# Nexys_2_Port_Expansion_Pack.net
KiCad netlist of a schematic drawn in EAGLE
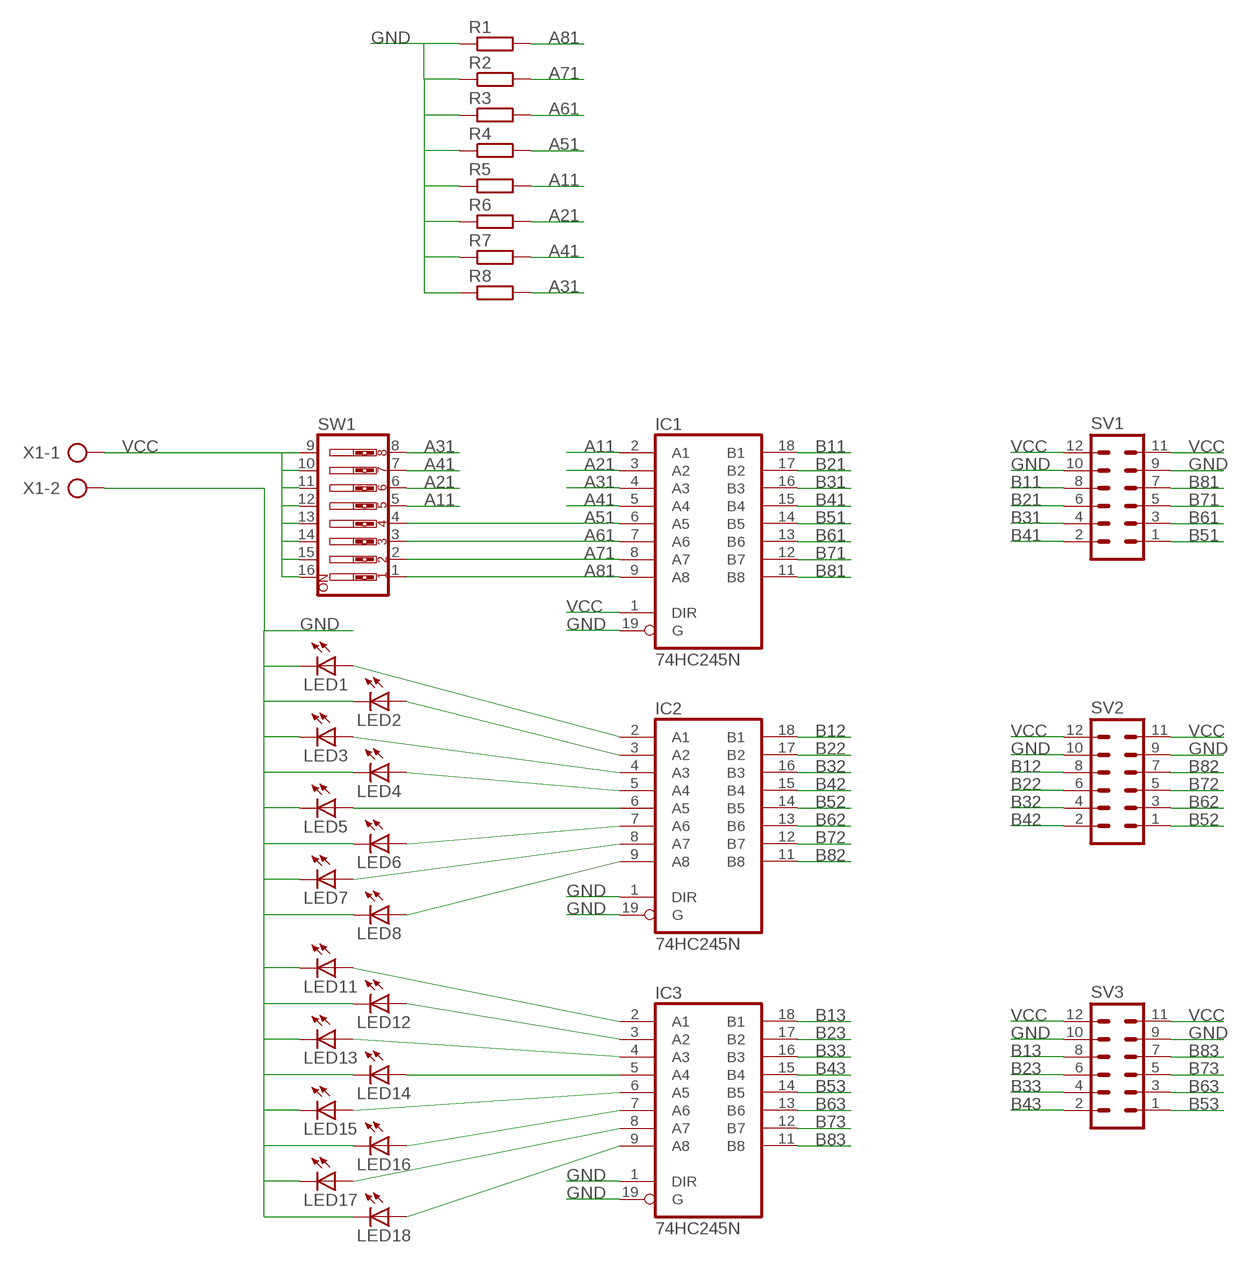
[diagram p0: schematic, sheet 1]

(export (version "E")
  (design (tool "Eeschema 10.0.6"))
  (components
    (comp (ref "IC1")
      (value "74HC245N")
      (footprint "eagle-import:DIL20")
      (libsource (lib "eagle-import") (part "74245NHC"))
    )
    (comp (ref "IC2")
      (value "74HC245N")
      (footprint "eagle-import:DIL20")
      (libsource (lib "eagle-import") (part "74245NHC"))
    )
    (comp (ref "IC3")
      (value "74HC245N")
      (footprint "eagle-import:DIL20")
      (libsource (lib "eagle-import") (part "74245NHC"))
    )
    (comp (ref "LED1")
      (value "LED3MM")
      (footprint "eagle-import:LED3MM")
      (libsource (lib "eagle-import") (part "LED3MM"))
    )
    (comp (ref "LED2")
      (value "LED3MM")
      (footprint "eagle-import:LED3MM")
      (libsource (lib "eagle-import") (part "LED3MM"))
    )
    (comp (ref "LED3")
      (value "LED3MM")
      (footprint "eagle-import:LED3MM")
      (libsource (lib "eagle-import") (part "LED3MM"))
    )
    (comp (ref "LED4")
      (value "LED3MM")
      (footprint "eagle-import:LED3MM")
      (libsource (lib "eagle-import") (part "LED3MM"))
    )
    (comp (ref "LED5")
      (value "LED3MM")
      (footprint "eagle-import:LED3MM")
      (libsource (lib "eagle-import") (part "LED3MM"))
    )
    (comp (ref "LED6")
      (value "LED3MM")
      (footprint "eagle-import:LED3MM")
      (libsource (lib "eagle-import") (part "LED3MM"))
    )
    (comp (ref "LED7")
      (value "LED3MM")
      (footprint "eagle-import:LED3MM")
      (libsource (lib "eagle-import") (part "LED3MM"))
    )
    (comp (ref "LED8")
      (value "LED3MM")
      (footprint "eagle-import:LED3MM")
      (libsource (lib "eagle-import") (part "LED3MM"))
    )
    (comp (ref "LED11")
      (value "LED3MM")
      (footprint "eagle-import:LED3MM")
      (libsource (lib "eagle-import") (part "LED3MM"))
    )
    (comp (ref "LED12")
      (value "LED3MM")
      (footprint "eagle-import:LED3MM")
      (libsource (lib "eagle-import") (part "LED3MM"))
    )
    (comp (ref "LED13")
      (value "LED3MM")
      (footprint "eagle-import:LED3MM")
      (libsource (lib "eagle-import") (part "LED3MM"))
    )
    (comp (ref "LED14")
      (value "LED3MM")
      (footprint "eagle-import:LED3MM")
      (libsource (lib "eagle-import") (part "LED3MM"))
    )
    (comp (ref "LED15")
      (value "LED3MM")
      (footprint "eagle-import:LED3MM")
      (libsource (lib "eagle-import") (part "LED3MM"))
    )
    (comp (ref "LED16")
      (value "LED3MM")
      (footprint "eagle-import:LED3MM")
      (libsource (lib "eagle-import") (part "LED3MM"))
    )
    (comp (ref "LED17")
      (value "LED3MM")
      (footprint "eagle-import:LED3MM")
      (libsource (lib "eagle-import") (part "LED3MM"))
    )
    (comp (ref "LED18")
      (value "LED3MM")
      (footprint "eagle-import:LED3MM")
      (libsource (lib "eagle-import") (part "LED3MM"))
    )
    (comp (ref "R1")
      (value "R-EU_0207/15")
      (footprint "eagle-import:0207_15")
      (libsource (lib "eagle-import") (part "R-EU_0207/15"))
    )
    (comp (ref "R2")
      (value "R-EU_0207/15")
      (footprint "eagle-import:0207_15")
      (libsource (lib "eagle-import") (part "R-EU_0207/15"))
    )
    (comp (ref "R3")
      (value "R-EU_0207/15")
      (footprint "eagle-import:0207_15")
      (libsource (lib "eagle-import") (part "R-EU_0207/15"))
    )
    (comp (ref "R4")
      (value "R-EU_0207/15")
      (footprint "eagle-import:0207_15")
      (libsource (lib "eagle-import") (part "R-EU_0207/15"))
    )
    (comp (ref "R5")
      (value "R-EU_0207/15")
      (footprint "eagle-import:0207_15")
      (libsource (lib "eagle-import") (part "R-EU_0207/15"))
    )
    (comp (ref "R6")
      (value "R-EU_0207/15")
      (footprint "eagle-import:0207_15")
      (libsource (lib "eagle-import") (part "R-EU_0207/15"))
    )
    (comp (ref "R7")
      (value "R-EU_0207/15")
      (footprint "eagle-import:0207_15")
      (libsource (lib "eagle-import") (part "R-EU_0207/15"))
    )
    (comp (ref "R8")
      (value "R-EU_0207/15")
      (footprint "eagle-import:0207_15")
      (libsource (lib "eagle-import") (part "R-EU_0207/15"))
    )
    (comp (ref "SV1")
      (value "MA06-2")
      (footprint "eagle-import:MA06-2")
      (libsource (lib "eagle-import") (part "MA06-2"))
    )
    (comp (ref "SV2")
      (value "MA06-2")
      (footprint "eagle-import:MA06-2")
      (libsource (lib "eagle-import") (part "MA06-2"))
    )
    (comp (ref "SV3")
      (value "MA06-2")
      (footprint "eagle-import:MA06-2")
      (libsource (lib "eagle-import") (part "MA06-2"))
    )
    (comp (ref "SW1")
      (value "SW_DIP-8")
      (footprint "eagle-import:EDG-08")
      (libsource (lib "eagle-import") (part "SW_DIP-8"))
    )
    (comp (ref "X1")
      (value "AK500/2")
      (footprint "eagle-import:AK500_2")
      (libsource (lib "eagle-import") (part "AK500/2"))
    )
  )
  (nets
    (net (code "1") (name "/A11") (class "Default")
      (node (ref "IC1") (pin "2") (pinfunction "A1_2") (pintype "bidirectional"))
      (node (ref "R5") (pin "2") (pinfunction "2_2") (pintype "passive"))
      (node (ref "SW1") (pin "5") (pinfunction "5_5") (pintype "passive"))
    )
    (net (code "2") (name "/A21") (class "Default")
      (node (ref "IC1") (pin "3") (pinfunction "A2_3") (pintype "bidirectional"))
      (node (ref "R6") (pin "2") (pinfunction "2_2") (pintype "passive"))
      (node (ref "SW1") (pin "6") (pinfunction "6_6") (pintype "passive"))
    )
    (net (code "3") (name "/A31") (class "Default")
      (node (ref "IC1") (pin "4") (pinfunction "A3_4") (pintype "bidirectional"))
      (node (ref "R8") (pin "2") (pinfunction "2_2") (pintype "passive"))
      (node (ref "SW1") (pin "8") (pinfunction "8_8") (pintype "passive"))
    )
    (net (code "4") (name "/A41") (class "Default")
      (node (ref "IC1") (pin "5") (pinfunction "A4_5") (pintype "bidirectional"))
      (node (ref "R7") (pin "2") (pinfunction "2_2") (pintype "passive"))
      (node (ref "SW1") (pin "7") (pinfunction "7_7") (pintype "passive"))
    )
    (net (code "5") (name "/A51") (class "Default")
      (node (ref "IC1") (pin "6") (pinfunction "A5_6") (pintype "bidirectional"))
      (node (ref "R4") (pin "2") (pinfunction "2_2") (pintype "passive"))
      (node (ref "SW1") (pin "4") (pinfunction "4_4") (pintype "passive"))
    )
    (net (code "6") (name "/A61") (class "Default")
      (node (ref "IC1") (pin "7") (pinfunction "A6_7") (pintype "bidirectional"))
      (node (ref "R3") (pin "2") (pinfunction "2_2") (pintype "passive"))
      (node (ref "SW1") (pin "3") (pinfunction "3_3") (pintype "passive"))
    )
    (net (code "7") (name "/A71") (class "Default")
      (node (ref "IC1") (pin "8") (pinfunction "A7_8") (pintype "bidirectional"))
      (node (ref "R2") (pin "2") (pinfunction "2_2") (pintype "passive"))
      (node (ref "SW1") (pin "2") (pinfunction "2_2") (pintype "passive"))
    )
    (net (code "8") (name "/A81") (class "Default")
      (node (ref "IC1") (pin "9") (pinfunction "A8_9") (pintype "bidirectional"))
      (node (ref "R1") (pin "2") (pinfunction "2_2") (pintype "passive"))
      (node (ref "SW1") (pin "1") (pinfunction "1_1") (pintype "passive"))
    )
    (net (code "9") (name "/B11") (class "Default")
      (node (ref "IC1") (pin "18") (pinfunction "B1_18") (pintype "bidirectional"))
      (node (ref "SV1") (pin "8") (pinfunction "8_8") (pintype "passive"))
    )
    (net (code "10") (name "/B12") (class "Default")
      (node (ref "IC2") (pin "18") (pinfunction "B1_18") (pintype "bidirectional"))
      (node (ref "SV2") (pin "8") (pinfunction "8_8") (pintype "passive"))
    )
    (net (code "11") (name "/B13") (class "Default")
      (node (ref "IC3") (pin "18") (pinfunction "B1_18") (pintype "bidirectional"))
      (node (ref "SV3") (pin "8") (pinfunction "8_8") (pintype "passive"))
    )
    (net (code "12") (name "/B21") (class "Default")
      (node (ref "IC1") (pin "17") (pinfunction "B2_17") (pintype "bidirectional"))
      (node (ref "SV1") (pin "6") (pinfunction "6_6") (pintype "passive"))
    )
    (net (code "13") (name "/B22") (class "Default")
      (node (ref "IC2") (pin "17") (pinfunction "B2_17") (pintype "bidirectional"))
      (node (ref "SV2") (pin "6") (pinfunction "6_6") (pintype "passive"))
    )
    (net (code "14") (name "/B23") (class "Default")
      (node (ref "IC3") (pin "17") (pinfunction "B2_17") (pintype "bidirectional"))
      (node (ref "SV3") (pin "6") (pinfunction "6_6") (pintype "passive"))
    )
    (net (code "15") (name "/B31") (class "Default")
      (node (ref "IC1") (pin "16") (pinfunction "B3_16") (pintype "bidirectional"))
      (node (ref "SV1") (pin "4") (pinfunction "4_4") (pintype "passive"))
    )
    (net (code "16") (name "/B32") (class "Default")
      (node (ref "IC2") (pin "16") (pinfunction "B3_16") (pintype "bidirectional"))
      (node (ref "SV2") (pin "4") (pinfunction "4_4") (pintype "passive"))
    )
    (net (code "17") (name "/B33") (class "Default")
      (node (ref "IC3") (pin "16") (pinfunction "B3_16") (pintype "bidirectional"))
      (node (ref "SV3") (pin "4") (pinfunction "4_4") (pintype "passive"))
    )
    (net (code "18") (name "/B41") (class "Default")
      (node (ref "IC1") (pin "15") (pinfunction "B4_15") (pintype "bidirectional"))
      (node (ref "SV1") (pin "2") (pinfunction "2_2") (pintype "passive"))
    )
    (net (code "19") (name "/B42") (class "Default")
      (node (ref "IC2") (pin "15") (pinfunction "B4_15") (pintype "bidirectional"))
      (node (ref "SV2") (pin "2") (pinfunction "2_2") (pintype "passive"))
    )
    (net (code "20") (name "/B43") (class "Default")
      (node (ref "IC3") (pin "15") (pinfunction "B4_15") (pintype "bidirectional"))
      (node (ref "SV3") (pin "2") (pinfunction "2_2") (pintype "passive"))
    )
    (net (code "21") (name "/B51") (class "Default")
      (node (ref "IC1") (pin "14") (pinfunction "B5_14") (pintype "bidirectional"))
      (node (ref "SV1") (pin "1") (pinfunction "1_1") (pintype "passive"))
    )
    (net (code "22") (name "/B52") (class "Default")
      (node (ref "IC2") (pin "14") (pinfunction "B5_14") (pintype "bidirectional"))
      (node (ref "SV2") (pin "1") (pinfunction "1_1") (pintype "passive"))
    )
    (net (code "23") (name "/B53") (class "Default")
      (node (ref "IC3") (pin "14") (pinfunction "B5_14") (pintype "bidirectional"))
      (node (ref "SV3") (pin "1") (pinfunction "1_1") (pintype "passive"))
    )
    (net (code "24") (name "/B61") (class "Default")
      (node (ref "IC1") (pin "13") (pinfunction "B6_13") (pintype "bidirectional"))
      (node (ref "SV1") (pin "3") (pinfunction "3_3") (pintype "passive"))
    )
    (net (code "25") (name "/B62") (class "Default")
      (node (ref "IC2") (pin "13") (pinfunction "B6_13") (pintype "bidirectional"))
      (node (ref "SV2") (pin "3") (pinfunction "3_3") (pintype "passive"))
    )
    (net (code "26") (name "/B63") (class "Default")
      (node (ref "IC3") (pin "13") (pinfunction "B6_13") (pintype "bidirectional"))
      (node (ref "SV3") (pin "3") (pinfunction "3_3") (pintype "passive"))
    )
    (net (code "27") (name "/B71") (class "Default")
      (node (ref "IC1") (pin "12") (pinfunction "B7_12") (pintype "bidirectional"))
      (node (ref "SV1") (pin "5") (pinfunction "5_5") (pintype "passive"))
    )
    (net (code "28") (name "/B72") (class "Default")
      (node (ref "IC2") (pin "12") (pinfunction "B7_12") (pintype "bidirectional"))
      (node (ref "SV2") (pin "5") (pinfunction "5_5") (pintype "passive"))
    )
    (net (code "29") (name "/B73") (class "Default")
      (node (ref "IC3") (pin "12") (pinfunction "B7_12") (pintype "bidirectional"))
      (node (ref "SV3") (pin "5") (pinfunction "5_5") (pintype "passive"))
    )
    (net (code "30") (name "/B81") (class "Default")
      (node (ref "IC1") (pin "11") (pinfunction "B8_11") (pintype "bidirectional"))
      (node (ref "SV1") (pin "7") (pinfunction "7_7") (pintype "passive"))
    )
    (net (code "31") (name "/B82") (class "Default")
      (node (ref "IC2") (pin "11") (pinfunction "B8_11") (pintype "bidirectional"))
      (node (ref "SV2") (pin "7") (pinfunction "7_7") (pintype "passive"))
    )
    (net (code "32") (name "/B83") (class "Default")
      (node (ref "IC3") (pin "11") (pinfunction "B8_11") (pintype "bidirectional"))
      (node (ref "SV3") (pin "7") (pinfunction "7_7") (pintype "passive"))
    )
    (net (code "33") (name "/GND") (class "Default")
      (node (ref "IC1") (pin "19") (pinfunction "G_19") (pintype "input"))
      (node (ref "IC2") (pin "1") (pinfunction "DIR_1") (pintype "input"))
      (node (ref "IC2") (pin "19") (pinfunction "G_19") (pintype "input"))
      (node (ref "IC3") (pin "1") (pinfunction "DIR_1") (pintype "input"))
      (node (ref "IC3") (pin "19") (pinfunction "G_19") (pintype "input"))
      (node (ref "LED1") (pin "K") (pinfunction "C_K") (pintype "passive"))
      (node (ref "LED11") (pin "K") (pinfunction "C_K") (pintype "passive"))
      (node (ref "LED12") (pin "K") (pinfunction "C_K") (pintype "passive"))
      (node (ref "LED13") (pin "K") (pinfunction "C_K") (pintype "passive"))
      (node (ref "LED14") (pin "K") (pinfunction "C_K") (pintype "passive"))
      (node (ref "LED15") (pin "K") (pinfunction "C_K") (pintype "passive"))
      (node (ref "LED16") (pin "K") (pinfunction "C_K") (pintype "passive"))
      (node (ref "LED17") (pin "K") (pinfunction "C_K") (pintype "passive"))
      (node (ref "LED18") (pin "K") (pinfunction "C_K") (pintype "passive"))
      (node (ref "LED2") (pin "K") (pinfunction "C_K") (pintype "passive"))
      (node (ref "LED3") (pin "K") (pinfunction "C_K") (pintype "passive"))
      (node (ref "LED4") (pin "K") (pinfunction "C_K") (pintype "passive"))
      (node (ref "LED5") (pin "K") (pinfunction "C_K") (pintype "passive"))
      (node (ref "LED6") (pin "K") (pinfunction "C_K") (pintype "passive"))
      (node (ref "LED7") (pin "K") (pinfunction "C_K") (pintype "passive"))
      (node (ref "LED8") (pin "K") (pinfunction "C_K") (pintype "passive"))
      (node (ref "R1") (pin "1") (pinfunction "1_1") (pintype "passive"))
      (node (ref "R2") (pin "1") (pinfunction "1_1") (pintype "passive"))
      (node (ref "R3") (pin "1") (pinfunction "1_1") (pintype "passive"))
      (node (ref "R4") (pin "1") (pinfunction "1_1") (pintype "passive"))
      (node (ref "R5") (pin "1") (pinfunction "1_1") (pintype "passive"))
      (node (ref "R6") (pin "1") (pinfunction "1_1") (pintype "passive"))
      (node (ref "R7") (pin "1") (pinfunction "1_1") (pintype "passive"))
      (node (ref "R8") (pin "1") (pinfunction "1_1") (pintype "passive"))
      (node (ref "SV1") (pin "10") (pinfunction "10_10") (pintype "passive"))
      (node (ref "SV1") (pin "9") (pinfunction "9_9") (pintype "passive"))
      (node (ref "SV2") (pin "10") (pinfunction "10_10") (pintype "passive"))
      (node (ref "SV2") (pin "9") (pinfunction "9_9") (pintype "passive"))
      (node (ref "SV3") (pin "10") (pinfunction "10_10") (pintype "passive"))
      (node (ref "SV3") (pin "9") (pinfunction "9_9") (pintype "passive"))
      (node (ref "X1") (pin "2") (pinfunction "KL_2") (pintype "passive"))
    )
    (net (code "34") (name "/VCC") (class "Default")
      (node (ref "IC1") (pin "1") (pinfunction "DIR_1") (pintype "input"))
      (node (ref "SV1") (pin "11") (pinfunction "11_11") (pintype "passive"))
      (node (ref "SV1") (pin "12") (pinfunction "12_12") (pintype "passive"))
      (node (ref "SV2") (pin "11") (pinfunction "11_11") (pintype "passive"))
      (node (ref "SV2") (pin "12") (pinfunction "12_12") (pintype "passive"))
      (node (ref "SV3") (pin "11") (pinfunction "11_11") (pintype "passive"))
      (node (ref "SV3") (pin "12") (pinfunction "12_12") (pintype "passive"))
      (node (ref "SW1") (pin "10") (pinfunction "10_10") (pintype "passive"))
      (node (ref "SW1") (pin "11") (pinfunction "11_11") (pintype "passive"))
      (node (ref "SW1") (pin "12") (pinfunction "12_12") (pintype "passive"))
      (node (ref "SW1") (pin "13") (pinfunction "13_13") (pintype "passive"))
      (node (ref "SW1") (pin "14") (pinfunction "14_14") (pintype "passive"))
      (node (ref "SW1") (pin "15") (pinfunction "15_15") (pintype "passive"))
      (node (ref "SW1") (pin "16") (pinfunction "16_16") (pintype "passive"))
      (node (ref "SW1") (pin "9") (pinfunction "9_9") (pintype "passive"))
      (node (ref "X1") (pin "1") (pinfunction "KL_1") (pintype "passive"))
    )
    (net (code "35") (name "Net-(IC2A-A1)") (class "Default")
      (node (ref "IC2") (pin "2") (pinfunction "A1_2") (pintype "bidirectional"))
      (node (ref "LED1") (pin "A") (pinfunction "A_A") (pintype "passive"))
    )
    (net (code "36") (name "Net-(IC2A-A2)") (class "Default")
      (node (ref "IC2") (pin "3") (pinfunction "A2_3") (pintype "bidirectional"))
      (node (ref "LED2") (pin "A") (pinfunction "A_A") (pintype "passive"))
    )
    (net (code "37") (name "Net-(IC2A-A3)") (class "Default")
      (node (ref "IC2") (pin "4") (pinfunction "A3_4") (pintype "bidirectional"))
      (node (ref "LED3") (pin "A") (pinfunction "A_A") (pintype "passive"))
    )
    (net (code "38") (name "Net-(IC2A-A4)") (class "Default")
      (node (ref "IC2") (pin "5") (pinfunction "A4_5") (pintype "bidirectional"))
      (node (ref "LED4") (pin "A") (pinfunction "A_A") (pintype "passive"))
    )
    (net (code "39") (name "Net-(IC2A-A5)") (class "Default")
      (node (ref "IC2") (pin "6") (pinfunction "A5_6") (pintype "bidirectional"))
      (node (ref "LED5") (pin "A") (pinfunction "A_A") (pintype "passive"))
    )
    (net (code "40") (name "Net-(IC2A-A6)") (class "Default")
      (node (ref "IC2") (pin "7") (pinfunction "A6_7") (pintype "bidirectional"))
      (node (ref "LED6") (pin "A") (pinfunction "A_A") (pintype "passive"))
    )
    (net (code "41") (name "Net-(IC2A-A7)") (class "Default")
      (node (ref "IC2") (pin "8") (pinfunction "A7_8") (pintype "bidirectional"))
      (node (ref "LED7") (pin "A") (pinfunction "A_A") (pintype "passive"))
    )
    (net (code "42") (name "Net-(IC2A-A8)") (class "Default")
      (node (ref "IC2") (pin "9") (pinfunction "A8_9") (pintype "bidirectional"))
      (node (ref "LED8") (pin "A") (pinfunction "A_A") (pintype "passive"))
    )
    (net (code "43") (name "Net-(IC3A-A1)") (class "Default")
      (node (ref "IC3") (pin "2") (pinfunction "A1_2") (pintype "bidirectional"))
      (node (ref "LED11") (pin "A") (pinfunction "A_A") (pintype "passive"))
    )
    (net (code "44") (name "Net-(IC3A-A2)") (class "Default")
      (node (ref "IC3") (pin "3") (pinfunction "A2_3") (pintype "bidirectional"))
      (node (ref "LED12") (pin "A") (pinfunction "A_A") (pintype "passive"))
    )
    (net (code "45") (name "Net-(IC3A-A3)") (class "Default")
      (node (ref "IC3") (pin "4") (pinfunction "A3_4") (pintype "bidirectional"))
      (node (ref "LED13") (pin "A") (pinfunction "A_A") (pintype "passive"))
    )
    (net (code "46") (name "Net-(IC3A-A4)") (class "Default")
      (node (ref "IC3") (pin "5") (pinfunction "A4_5") (pintype "bidirectional"))
      (node (ref "LED14") (pin "A") (pinfunction "A_A") (pintype "passive"))
    )
    (net (code "47") (name "Net-(IC3A-A5)") (class "Default")
      (node (ref "IC3") (pin "6") (pinfunction "A5_6") (pintype "bidirectional"))
      (node (ref "LED15") (pin "A") (pinfunction "A_A") (pintype "passive"))
    )
    (net (code "48") (name "Net-(IC3A-A6)") (class "Default")
      (node (ref "IC3") (pin "7") (pinfunction "A6_7") (pintype "bidirectional"))
      (node (ref "LED16") (pin "A") (pinfunction "A_A") (pintype "passive"))
    )
    (net (code "49") (name "Net-(IC3A-A7)") (class "Default")
      (node (ref "IC3") (pin "8") (pinfunction "A7_8") (pintype "bidirectional"))
      (node (ref "LED17") (pin "A") (pinfunction "A_A") (pintype "passive"))
    )
    (net (code "50") (name "Net-(IC3A-A8)") (class "Default")
      (node (ref "IC3") (pin "9") (pinfunction "A8_9") (pintype "bidirectional"))
      (node (ref "LED18") (pin "A") (pinfunction "A_A") (pintype "passive"))
    )
  )
)
